# DRF1605_KIT.net
KiCad netlist of a schematic drawn in Altium Designer
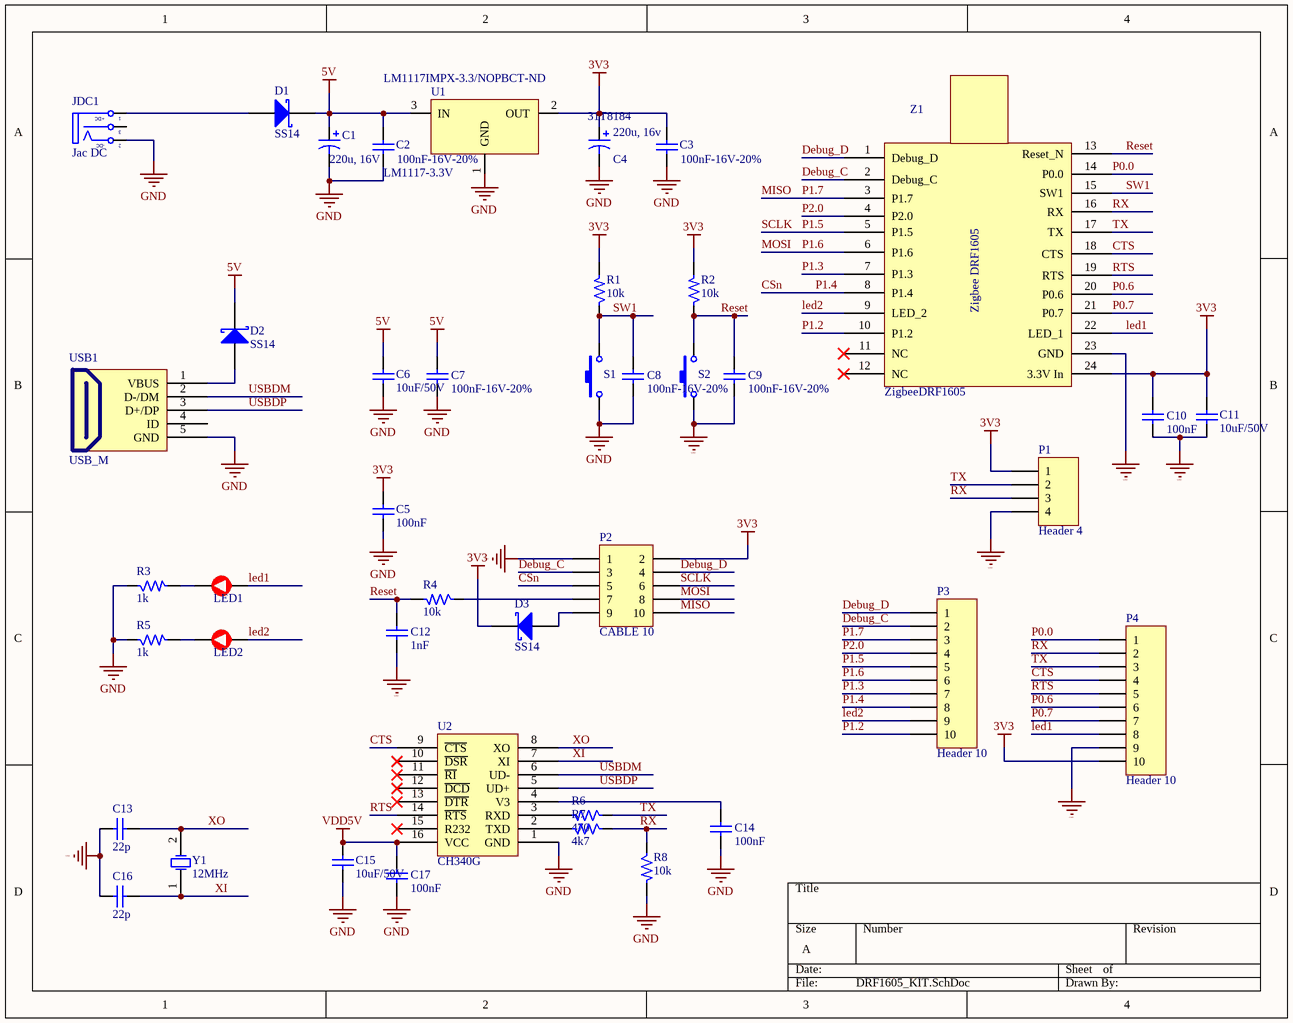
[diagram p0: DRF1605_KIT.SchDoc]

(export (version "E")
  (design (tool "Eeschema 10.0.6"))
  (components
    (comp (ref "C1")
      (value "220u, 16V")
      (footprint "ST:CAP TANTALUM 7343")
      (description "Polarized Capacitor (Surface Mount)")
      (fields
        (field (name "MANUFACTURER") "Kemet")
        (field (name "MANUFACTURER PART NUMBER") "C0603C103K5RACTU")
        (field (name "PUBLISHER") "Altium Limited")
      )
      (libsource (lib "Miscellaneous Devices") (part "Cap Pol3"))
    )
    (comp (ref "C2")
      (value "100nF-16V-20%")
      (footprint "C0805")
      (description "CAP CER 0.1UF 16V Y5V 0603")
      (fields
        (field (name "MANUFACTURER") "Yageo")
        (field (name "DIGI-KEY PART NUMBER") "311-1369-1-ND")
        (field (name "PUBLISHER") "Altium Limited")
      )
      (libsource (lib "Miscellaneous Devices") (part "Cap"))
    )
    (comp (ref "C3")
      (value "100nF-16V-20%")
      (footprint "C0805")
      (description "CAP CER 0.1UF 16V Y5V 0603")
      (fields
        (field (name "MANUFACTURER") "Yageo")
        (field (name "DIGI-KEY PART NUMBER") "311-1369-1-ND")
        (field (name "PUBLISHER") "Altium Limited")
      )
      (libsource (lib "Miscellaneous Devices") (part "Cap"))
    )
    (comp (ref "C4")
      (value "220u, 16v")
      (footprint "CAP TANTALUM 7343")
      (description "Polarized Capacitor (Surface Mount)")
      (fields (field (name "SUPPLIER PART NUMBER 1") "31T8184") (field (name "PUBLISHER") "Altium Limited"))
      (libsource (lib "Miscellaneous Devices") (part "Cap Pol3"))
    )
    (comp (ref "C5")
      (value "100nF")
      (footprint "C0805")
      (description "CAP CER 0.1UF 16V Y5V 0603")
      (fields
        (field (name "MANUFACTURER") "Yageo")
        (field (name "DIGI-KEY PART NUMBER") "311-1369-1-ND")
        (field (name "PUBLISHER") "Altium Limited")
      )
      (libsource (lib "Miscellaneous Devices") (part "Cap"))
    )
    (comp (ref "C6")
      (value "10uF/50V")
      (footprint "C1206")
      (description "Capacitor 100n 16V 0603")
      (fields (field (name "PUBLISHER") "Altium Limited"))
      (libsource (lib "Capacitor") (part "Cap Semi"))
    )
    (comp (ref "C7")
      (value "100nF-16V-20%")
      (footprint "C0805")
      (description "CAP CER 0.1UF 16V Y5V 0603")
      (fields
        (field (name "MANUFACTURER") "Yageo")
        (field (name "DIGI-KEY PART NUMBER") "311-1369-1-ND")
        (field (name "PUBLISHER") "Altium Limited")
      )
      (libsource (lib "Miscellaneous Devices") (part "Cap"))
    )
    (comp (ref "C8")
      (value "100nF-16V-20%")
      (footprint "C0805")
      (description "CAP CER 0.1UF 16V Y5V 0603")
      (fields
        (field (name "MANUFACTURER") "Yageo")
        (field (name "DIGI-KEY PART NUMBER") "311-1369-1-ND")
        (field (name "PUBLISHER") "Altium Limited")
      )
      (libsource (lib "Miscellaneous Devices") (part "Cap"))
    )
    (comp (ref "C9")
      (value "100nF-16V-20%")
      (footprint "C0805")
      (description "CAP CER 0.1UF 16V Y5V 0603")
      (fields
        (field (name "MANUFACTURER") "Yageo")
        (field (name "DIGI-KEY PART NUMBER") "311-1369-1-ND")
        (field (name "PUBLISHER") "Altium Limited")
      )
      (libsource (lib "Miscellaneous Devices") (part "Cap"))
    )
    (comp (ref "C10")
      (value "100nF")
      (footprint "C0805")
      (description "CAP CER 0.1UF 16V Y5V 0603")
      (fields
        (field (name "MANUFACTURER") "Yageo")
        (field (name "DIGI-KEY PART NUMBER") "311-1369-1-ND")
        (field (name "PUBLISHER") "Altium Limited")
      )
      (libsource (lib "Miscellaneous Devices") (part "Cap"))
    )
    (comp (ref "C11")
      (value "10uF/50V")
      (footprint "C1206")
      (description "Capacitor 100n 16V 0603")
      (fields (field (name "PUBLISHER") "Altium Limited"))
      (libsource (lib "Capacitor") (part "Cap Semi"))
    )
    (comp (ref "C12")
      (value "1nF")
      (footprint "C0805")
      (description "CAP CER 0.1UF 16V Y5V 0603")
      (fields
        (field (name "MANUFACTURER") "Yageo")
        (field (name "DIGI-KEY PART NUMBER") "311-1369-1-ND")
        (field (name "PUBLISHER") "Altium Limited")
      )
      (libsource (lib "Miscellaneous Devices") (part "Cap"))
    )
    (comp (ref "C13")
      (value "22p")
      (footprint "C0805")
      (description "Capacitor (Semiconductor SIM Model)")
      (fields (field (name "PUBLISHER") "Altium Limited"))
      (libsource (lib "Miscellaneous Devices") (part "Cap Semi"))
    )
    (comp (ref "C14")
      (value "100nF")
      (footprint "C0805")
      (description "CAP CER 0.1UF 16V Y5V 0603")
      (fields
        (field (name "MANUFACTURER") "Yageo")
        (field (name "DIGI-KEY PART NUMBER") "311-1369-1-ND")
        (field (name "PUBLISHER") "Altium Limited")
      )
      (libsource (lib "Miscellaneous Devices") (part "Cap"))
    )
    (comp (ref "C15")
      (value "10uF/50V")
      (footprint "C1206")
      (description "Capacitor 100n 16V 0603")
      (fields (field (name "PUBLISHER") "Altium Limited"))
      (libsource (lib "Capacitor") (part "Cap Semi"))
    )
    (comp (ref "C16")
      (value "22p")
      (footprint "C0805")
      (description "Capacitor (Semiconductor SIM Model)")
      (fields (field (name "PUBLISHER") "Altium Limited"))
      (libsource (lib "Miscellaneous Devices") (part "Cap Semi"))
    )
    (comp (ref "C17")
      (value "100nF")
      (footprint "C0805")
      (description "CAP CER 0.1UF 16V Y5V 0603")
      (fields
        (field (name "MANUFACTURER") "Yageo")
        (field (name "DIGI-KEY PART NUMBER") "311-1369-1-ND")
        (field (name "PUBLISHER") "Altium Limited")
      )
      (libsource (lib "Miscellaneous Devices") (part "Cap"))
    )
    (comp (ref "D1")
      (value "SS14")
      (footprint "DO-214AC (SMA)")
      (description "Schottky Diode")
      (fields (field (name "PUBLISHER") "Altium Limited"))
      (libsource (lib "Miscellaneous Devices") (part "D Schottky"))
    )
    (comp (ref "D2")
      (value "SS14")
      (footprint "DO-214AC (SMA)")
      (description "Schottky Diode")
      (fields (field (name "PUBLISHER") "Altium Limited"))
      (libsource (lib "Miscellaneous Devices") (part "D Schottky"))
    )
    (comp (ref "D3")
      (value "SS14")
      (footprint "DO-214AC (SMA)")
      (description "Schottky Diode")
      (fields (field (name "PUBLISHER") "Altium Limited"))
      (libsource (lib "Miscellaneous Devices") (part "D Schottky"))
    )
    (comp (ref "JDC1")
      (value "Jac DC")
      (footprint "DC-IN")
      (description "Jac DC input")
      (libsource (lib "syhaunguyen") (part "DCIN"))
    )
    (comp (ref "LED1")
      (value "LedBlue5")
      (footprint "LedBlue5")
      (description "LED")
      (fields (field (name "MANUFACTURER") "Harvatek"))
      (libsource (lib "SS_Basic") (part "Led"))
    )
    (comp (ref "LED2")
      (value "LedRed5")
      (footprint "LedRed5")
      (description "LED")
      (fields (field (name "MANUFACTURER") "Harvatek"))
      (libsource (lib "SS_Basic") (part "Led"))
    )
    (comp (ref "P1")
      (value "Header 4")
      (footprint "HDR1X4")
      (description "Header, 4-Pin")
      (fields (field (name "PUBLISHER") "Altium Limited"))
      (libsource (lib "SS_Con") (part "Header 4"))
    )
    (comp (ref "P2")
      (value "CABLE 10")
      (footprint "PcbLib2:CABLE 10")
      (description "Header, 5-Pin, Dual row")
      (fields (field (name "PUBLISHER") "Altium Limited"))
      (libsource (lib "mLibrary") (part "CABLE 10"))
    )
    (comp (ref "P3")
      (value "Header 10")
      (footprint "HDR1X10")
      (description "Header, 10-Pin")
      (fields (field (name "PUBLISHER") "Altium Limited"))
      (libsource (lib "SS_Con") (part "Header 10"))
    )
    (comp (ref "P4")
      (value "Header 10")
      (footprint "HDR1X10")
      (description "Header, 10-Pin")
      (fields (field (name "PUBLISHER") "Altium Limited"))
      (libsource (lib "SS_Con") (part "Header 10"))
    )
    (comp (ref "R1")
      (value "10k")
      (footprint "R0805")
      (description "Resistor SMD")
      (fields (field (name "MANUFACTURER") "UniOhm"))
      (libsource (lib "Schlib1") (part "RM"))
    )
    (comp (ref "R2")
      (value "10k")
      (footprint "R0805")
      (description "Resistor SMD")
      (fields (field (name "MANUFACTURER") "UniOhm"))
      (libsource (lib "Schlib1") (part "RM"))
    )
    (comp (ref "R3")
      (value "1k")
      (footprint "R0805")
      (description "Resistor SMD")
      (fields (field (name "MANUFACTURER") "UniOhm"))
      (libsource (lib "Schlib1") (part "RM"))
    )
    (comp (ref "R4")
      (value "10k")
      (footprint "R0805")
      (description "Resistor SMD")
      (fields (field (name "MANUFACTURER") "UniOhm"))
      (libsource (lib "Schlib1") (part "RM"))
    )
    (comp (ref "R5")
      (value "1k")
      (footprint "R0805")
      (description "Resistor SMD")
      (fields (field (name "MANUFACTURER") "UniOhm"))
      (libsource (lib "Schlib1") (part "RM"))
    )
    (comp (ref "R6")
      (value "470")
      (footprint "R0805")
      (description "Resistor SMD")
      (fields (field (name "MANUFACTURER") "UniOhm"))
      (libsource (lib "Schlib1") (part "RM"))
    )
    (comp (ref "R7")
      (value "4k7")
      (footprint "R0805")
      (description "Resistor SMD")
      (fields (field (name "MANUFACTURER") "UniOhm"))
      (libsource (lib "Schlib1") (part "RM"))
    )
    (comp (ref "R8")
      (value "10k")
      (footprint "R0805")
      (description "Resistor SMD")
      (fields (field (name "MANUFACTURER") "UniOhm"))
      (libsource (lib "Schlib1") (part "RM"))
    )
    (comp (ref "S1")
      (value "SW-SMD")
      (footprint "Button Tactile Switch")
      (description "Switch")
      (fields (field (name "PUBLISHER") "Altium Limited"))
      (libsource (lib "Schematic") (part "SW-SMD"))
    )
    (comp (ref "S2")
      (value "SW-SMD")
      (footprint "Button Tactile Switch")
      (description "Switch")
      (fields (field (name "PUBLISHER") "Altium Limited"))
      (libsource (lib "Schematic") (part "SW-SMD"))
    )
    (comp (ref "U1")
      (value "LM1117-3.3V")
      (footprint "LM1117-SOP")
      (description "800mA Low-Dropout Linear Regulator")
      (fields
        (field (name "SUPPLIER PART NUMBER 1") "LM1117IMPX-3.3/NOPBCT-ND")
        (field (name "CREATOR") "Nguyen Ba Bien")
      )
      (libsource (lib "General IC") (part "LM1117"))
    )
    (comp (ref "U2")
      (value "CH340G")
      (footprint "SOP-16")
      (description "CH340G USB to serial (UART) bridge")
      (libsource (lib "Vowstar_IC_General") (part "CH340G"))
    )
    (comp (ref "USB1") (value "USB_M") (footprint "USB_B_MINI_SMD") (libsource (lib "SS_Con") (part "USB_M")))
    (comp (ref "Y1")
      (value "12MHz")
      (footprint "ST:XT2 SMD")
      (description "Crystal Oscillator")
      (fields (field (name "PUBLISHER") "Altium Limited"))
      (libsource (lib "Miscellaneous Devices") (part "XTAL"))
    )
    (comp (ref "Z1")
      (value "ZigbeeDRF1605")
      (footprint "PcbLib2:DRF1605")
      (libsource (lib "module-lib") (part "DRF1605"))
    )
  )
  (nets
    (net (code "1") (name "/CSn") (class "Default")
      (node (ref "P2") (pin "5") (pinfunction "5_5") (pintype "passive"))
      (node (ref "P3") (pin "8") (pinfunction "8_8") (pintype "passive"))
      (node (ref "Z1") (pin "8") (pinfunction "P1.4_8") (pintype "passive"))
    )
    (net (code "2") (name "/CTS") (class "Default")
      (node (ref "P4") (pin "4") (pinfunction "4_4") (pintype "passive"))
      (node (ref "U2") (pin "9") (pinfunction "~{CTS}_9") (pintype "passive"))
      (node (ref "Z1") (pin "18") (pinfunction "CTS_18") (pintype "passive"))
    )
    (net (code "3") (name "/Debug_C") (class "Default")
      (node (ref "P2") (pin "3") (pinfunction "3_3") (pintype "passive"))
      (node (ref "P3") (pin "2") (pinfunction "2_2") (pintype "passive"))
      (node (ref "Z1") (pin "2") (pinfunction "Debug_C_2") (pintype "passive"))
    )
    (net (code "4") (name "/Debug_D") (class "Default")
      (node (ref "P2") (pin "4") (pinfunction "4_4") (pintype "passive"))
      (node (ref "P3") (pin "1") (pinfunction "1_1") (pintype "passive"))
      (node (ref "Z1") (pin "1") (pinfunction "Debug_D_1") (pintype "passive"))
    )
    (net (code "5") (name "/MISO") (class "Default")
      (node (ref "P2") (pin "10") (pinfunction "10_10") (pintype "passive"))
      (node (ref "P3") (pin "3") (pinfunction "3_3") (pintype "passive"))
      (node (ref "Z1") (pin "3") (pinfunction "P1.7_3") (pintype "passive"))
    )
    (net (code "6") (name "/MOSI") (class "Default")
      (node (ref "P2") (pin "8") (pinfunction "8_8") (pintype "passive"))
      (node (ref "P3") (pin "6") (pinfunction "6_6") (pintype "passive"))
      (node (ref "Z1") (pin "6") (pinfunction "P1.6_6") (pintype "passive"))
    )
    (net (code "7") (name "/P0.0") (class "Default")
      (node (ref "P4") (pin "1") (pinfunction "1_1") (pintype "passive"))
      (node (ref "Z1") (pin "14") (pinfunction "P0.0_14") (pintype "passive"))
    )
    (net (code "8") (name "/P0.6") (class "Default")
      (node (ref "P4") (pin "6") (pinfunction "6_6") (pintype "passive"))
      (node (ref "Z1") (pin "20") (pinfunction "P0.6_20") (pintype "passive"))
    )
    (net (code "9") (name "/P0.7") (class "Default")
      (node (ref "P4") (pin "7") (pinfunction "7_7") (pintype "passive"))
      (node (ref "Z1") (pin "21") (pinfunction "P0.7_21") (pintype "passive"))
    )
    (net (code "10") (name "/P1.2") (class "Default")
      (node (ref "P3") (pin "10") (pinfunction "10_10") (pintype "passive"))
      (node (ref "Z1") (pin "10") (pinfunction "P1.2_10") (pintype "passive"))
    )
    (net (code "11") (name "/P1.3") (class "Default")
      (node (ref "P3") (pin "7") (pinfunction "7_7") (pintype "passive"))
      (node (ref "Z1") (pin "7") (pinfunction "P1.3_7") (pintype "passive"))
    )
    (net (code "12") (name "/P1.5") (class "Default")
      (node (ref "P2") (pin "6") (pinfunction "6_6") (pintype "passive"))
      (node (ref "P3") (pin "5") (pinfunction "5_5") (pintype "passive"))
      (node (ref "Z1") (pin "5") (pinfunction "P1.5_5") (pintype "passive"))
    )
    (net (code "13") (name "/P2.0") (class "Default")
      (node (ref "P3") (pin "4") (pinfunction "4_4") (pintype "passive"))
      (node (ref "Z1") (pin "4") (pinfunction "P2.0_4") (pintype "passive"))
    )
    (net (code "14") (name "/RTS") (class "Default")
      (node (ref "P4") (pin "5") (pinfunction "5_5") (pintype "passive"))
      (node (ref "U2") (pin "14") (pinfunction "~{RTS}_14") (pintype "passive"))
      (node (ref "Z1") (pin "19") (pinfunction "RTS_19") (pintype "passive"))
    )
    (net (code "15") (name "/RX") (class "Default")
      (node (ref "P1") (pin "3") (pinfunction "3_3") (pintype "passive"))
      (node (ref "P4") (pin "2") (pinfunction "2_2") (pintype "passive"))
      (node (ref "R7") (pin "1") (pinfunction "1_1") (pintype "passive"))
      (node (ref "R8") (pin "1") (pinfunction "1_1") (pintype "passive"))
      (node (ref "Z1") (pin "16") (pinfunction "RX_16") (pintype "passive"))
    )
    (net (code "16") (name "/Reset") (class "Default")
      (node (ref "C12") (pin "1") (pinfunction "1_1") (pintype "passive"))
      (node (ref "C9") (pin "1") (pinfunction "1_1") (pintype "passive"))
      (node (ref "R2") (pin "1") (pinfunction "1_1") (pintype "passive"))
      (node (ref "R4") (pin "2") (pinfunction "2_2") (pintype "passive"))
      (node (ref "S2") (pin "2") (pinfunction "2_2") (pintype "passive"))
      (node (ref "Z1") (pin "13") (pinfunction "Reset_N_13") (pintype "passive"))
    )
    (net (code "17") (name "/SW1") (class "Default")
      (node (ref "C8") (pin "1") (pinfunction "1_1") (pintype "passive"))
      (node (ref "R1") (pin "1") (pinfunction "1_1") (pintype "passive"))
      (node (ref "S1") (pin "2") (pinfunction "2_2") (pintype "passive"))
      (node (ref "Z1") (pin "15") (pinfunction "SW1_15") (pintype "passive"))
    )
    (net (code "18") (name "/TX") (class "Default")
      (node (ref "P1") (pin "2") (pinfunction "2_2") (pintype "passive"))
      (node (ref "P4") (pin "3") (pinfunction "3_3") (pintype "passive"))
      (node (ref "R6") (pin "1") (pinfunction "1_1") (pintype "passive"))
      (node (ref "Z1") (pin "17") (pinfunction "TX_17") (pintype "passive"))
    )
    (net (code "19") (name "/USBDM") (class "Default")
      (node (ref "U2") (pin "6") (pinfunction "UD-_6") (pintype "passive"))
      (node (ref "USB1") (pin "2") (pinfunction "D-/DM_2") (pintype "passive"))
    )
    (net (code "20") (name "/USBDP") (class "Default")
      (node (ref "U2") (pin "5") (pinfunction "UD+_5") (pintype "passive"))
      (node (ref "USB1") (pin "3") (pinfunction "D+/DP_3") (pintype "passive"))
    )
    (net (code "21") (name "/XI") (class "Default")
      (node (ref "C16") (pin "2") (pinfunction "2_2") (pintype "passive"))
      (node (ref "U2") (pin "7") (pinfunction "XI_7") (pintype "passive"))
      (node (ref "Y1") (pin "1") (pinfunction "OSC1_1") (pintype "passive"))
    )
    (net (code "22") (name "/XO") (class "Default")
      (node (ref "C13") (pin "2") (pinfunction "2_2") (pintype "passive"))
      (node (ref "U2") (pin "8") (pinfunction "XO_8") (pintype "passive"))
      (node (ref "Y1") (pin "2") (pinfunction "OSC2_2") (pintype "passive"))
    )
    (net (code "23") (name "/led1") (class "Default")
      (node (ref "LED1") (pin "2") (pinfunction "2_2") (pintype "passive"))
      (node (ref "P4") (pin "8") (pinfunction "8_8") (pintype "passive"))
      (node (ref "Z1") (pin "22") (pinfunction "LED_1_22") (pintype "passive"))
    )
    (net (code "24") (name "/led2") (class "Default")
      (node (ref "LED2") (pin "2") (pinfunction "2_2") (pintype "passive"))
      (node (ref "P3") (pin "9") (pinfunction "9_9") (pintype "passive"))
      (node (ref "Z1") (pin "9") (pinfunction "LED_2_9") (pintype "passive"))
    )
    (net (code "25") (name "3V3") (class "Default")
      (node (ref "C10") (pin "1") (pinfunction "1_1") (pintype "passive"))
      (node (ref "C11") (pin "1") (pinfunction "1_1") (pintype "passive"))
      (node (ref "C3") (pin "1") (pinfunction "1_1") (pintype "passive"))
      (node (ref "C4") (pin "1") (pinfunction "1_1") (pintype "passive"))
      (node (ref "C5") (pin "1") (pinfunction "1_1") (pintype "passive"))
      (node (ref "D3") (pin "2") (pinfunction "K_2") (pintype "passive"))
      (node (ref "P1") (pin "1") (pinfunction "1_1") (pintype "passive"))
      (node (ref "P2") (pin "2") (pinfunction "2_2") (pintype "passive"))
      (node (ref "P4") (pin "10") (pinfunction "10_10") (pintype "passive"))
      (node (ref "R1") (pin "2") (pinfunction "2_2") (pintype "passive"))
      (node (ref "R2") (pin "2") (pinfunction "2_2") (pintype "passive"))
      (node (ref "U1") (pin "2") (pinfunction "OUT_2") (pintype "passive"))
      (node (ref "Z1") (pin "24") (pinfunction "3.3V_In_24") (pintype "passive"))
    )
    (net (code "26") (name "5V") (class "Default")
      (node (ref "C1") (pin "1") (pinfunction "1_1") (pintype "passive"))
      (node (ref "C2") (pin "1") (pinfunction "1_1") (pintype "passive"))
      (node (ref "C6") (pin "1") (pinfunction "1_1") (pintype "passive"))
      (node (ref "C7") (pin "1") (pinfunction "1_1") (pintype "passive"))
      (node (ref "D1") (pin "2") (pinfunction "K_2") (pintype "passive"))
      (node (ref "D2") (pin "2") (pinfunction "K_2") (pintype "passive"))
      (node (ref "U1") (pin "3") (pinfunction "IN_3") (pintype "passive"))
    )
    (net (code "27") (name "GND") (class "Default")
      (node (ref "C1") (pin "2") (pinfunction "2_2") (pintype "passive"))
      (node (ref "C10") (pin "2") (pinfunction "2_2") (pintype "passive"))
      (node (ref "C11") (pin "2") (pinfunction "2_2") (pintype "passive"))
      (node (ref "C12") (pin "2") (pinfunction "2_2") (pintype "passive"))
      (node (ref "C13") (pin "1") (pinfunction "1_1") (pintype "passive"))
      (node (ref "C14") (pin "2") (pinfunction "2_2") (pintype "passive"))
      (node (ref "C15") (pin "2") (pinfunction "2_2") (pintype "passive"))
      (node (ref "C16") (pin "1") (pinfunction "1_1") (pintype "passive"))
      (node (ref "C17") (pin "2") (pinfunction "2_2") (pintype "passive"))
      (node (ref "C2") (pin "2") (pinfunction "2_2") (pintype "passive"))
      (node (ref "C3") (pin "2") (pinfunction "2_2") (pintype "passive"))
      (node (ref "C4") (pin "2") (pinfunction "2_2") (pintype "passive"))
      (node (ref "C5") (pin "2") (pinfunction "2_2") (pintype "passive"))
      (node (ref "C6") (pin "2") (pinfunction "2_2") (pintype "passive"))
      (node (ref "C7") (pin "2") (pinfunction "2_2") (pintype "passive"))
      (node (ref "C8") (pin "2") (pinfunction "2_2") (pintype "passive"))
      (node (ref "C9") (pin "2") (pinfunction "2_2") (pintype "passive"))
      (node (ref "JDC1") (pin "2") (pinfunction "TN_2") (pintype "passive"))
      (node (ref "P1") (pin "4") (pinfunction "4_4") (pintype "passive"))
      (node (ref "P2") (pin "1") (pinfunction "1_1") (pintype "passive"))
      (node (ref "P4") (pin "9") (pinfunction "9_9") (pintype "passive"))
      (node (ref "R3") (pin "1") (pinfunction "1_1") (pintype "passive"))
      (node (ref "R5") (pin "1") (pinfunction "1_1") (pintype "passive"))
      (node (ref "R8") (pin "2") (pinfunction "2_2") (pintype "passive"))
      (node (ref "S1") (pin "1") (pinfunction "1_1") (pintype "passive"))
      (node (ref "S2") (pin "1") (pinfunction "1_1") (pintype "passive"))
      (node (ref "U1") (pin "1") (pinfunction "GND_1") (pintype "passive"))
      (node (ref "U2") (pin "1") (pinfunction "GND_1") (pintype "passive"))
      (node (ref "USB1") (pin "5") (pinfunction "GND_5") (pintype "passive"))
      (node (ref "Z1") (pin "23") (pinfunction "GND_23") (pintype "passive"))
    )
    (net (code "28") (name "Net-(D1-A)") (class "Default")
      (node (ref "D1") (pin "1") (pinfunction "A_1") (pintype "passive"))
      (node (ref "JDC1") (pin "1") (pinfunction "T_1") (pintype "passive"))
    )
    (net (code "29") (name "Net-(D2-A)") (class "Default")
      (node (ref "D2") (pin "1") (pinfunction "A_1") (pintype "passive"))
      (node (ref "USB1") (pin "1") (pinfunction "VBUS_1") (pintype "passive"))
    )
    (net (code "30") (name "Net-(D3-A)") (class "Default")
      (node (ref "D3") (pin "1") (pinfunction "A_1") (pintype "passive"))
      (node (ref "P2") (pin "9") (pinfunction "9_9") (pintype "passive"))
    )
    (net (code "31") (name "Net-(LED1-Pad1)") (class "Default")
      (node (ref "LED1") (pin "1") (pinfunction "1_1") (pintype "passive"))
      (node (ref "R3") (pin "2") (pinfunction "2_2") (pintype "passive"))
    )
    (net (code "32") (name "Net-(LED2-Pad1)") (class "Default")
      (node (ref "LED2") (pin "1") (pinfunction "1_1") (pintype "passive"))
      (node (ref "R5") (pin "2") (pinfunction "2_2") (pintype "passive"))
    )
    (net (code "33") (name "Net-(P2-Pad7)") (class "Default")
      (node (ref "P2") (pin "7") (pinfunction "7_7") (pintype "passive"))
      (node (ref "R4") (pin "1") (pinfunction "1_1") (pintype "passive"))
    )
    (net (code "34") (name "Net-(U2-RXD)") (class "Default")
      (node (ref "R6") (pin "2") (pinfunction "2_2") (pintype "passive"))
      (node (ref "U2") (pin "3") (pinfunction "RXD_3") (pintype "passive"))
    )
    (net (code "35") (name "Net-(U2-TXD)") (class "Default")
      (node (ref "R7") (pin "2") (pinfunction "2_2") (pintype "passive"))
      (node (ref "U2") (pin "2") (pinfunction "TXD_2") (pintype "passive"))
    )
    (net (code "36") (name "Net-(U2-V3)") (class "Default")
      (node (ref "C14") (pin "1") (pinfunction "1_1") (pintype "passive"))
      (node (ref "U2") (pin "4") (pinfunction "V3_4") (pintype "passive"))
    )
    (net (code "37") (name "VDD5V") (class "Default")
      (node (ref "C15") (pin "1") (pinfunction "1_1") (pintype "passive"))
      (node (ref "C17") (pin "1") (pinfunction "1_1") (pintype "passive"))
      (node (ref "U2") (pin "16") (pinfunction "VCC_16") (pintype "passive"))
    )
    (net (code "38") (name "unconnected-(JDC1-S-Pad3)") (class "Default")
      (node (ref "JDC1") (pin "3") (pinfunction "S_3") (pintype "power_in"))
    )
    (net (code "39") (name "unconnected-(U2-R232-Pad15)") (class "Default")
      (node (ref "U2") (pin "15") (pinfunction "R232_15") (pintype "passive+no_connect"))
    )
    (net (code "40") (name "unconnected-(U2-~{DCD}-Pad12)") (class "Default")
      (node (ref "U2") (pin "12") (pinfunction "~{DCD}_12") (pintype "passive+no_connect"))
    )
    (net (code "41") (name "unconnected-(U2-~{DSR}-Pad10)") (class "Default")
      (node (ref "U2") (pin "10") (pinfunction "~{DSR}_10") (pintype "passive+no_connect"))
    )
    (net (code "42") (name "unconnected-(U2-~{DTR}-Pad13)") (class "Default")
      (node (ref "U2") (pin "13") (pinfunction "~{DTR}_13") (pintype "passive+no_connect"))
    )
    (net (code "43") (name "unconnected-(U2-~{RI}-Pad11)") (class "Default")
      (node (ref "U2") (pin "11") (pinfunction "~{RI}_11") (pintype "passive+no_connect"))
    )
    (net (code "44") (name "unconnected-(USB1-ID-Pad4)") (class "Default")
      (node (ref "USB1") (pin "4") (pinfunction "ID_4") (pintype "passive"))
    )
    (net (code "45") (name "unconnected-(Z1-NC-Pad11)") (class "Default")
      (node (ref "Z1") (pin "11") (pinfunction "NC_11") (pintype "passive+no_connect"))
    )
    (net (code "46") (name "unconnected-(Z1-NC-Pad12)") (class "Default")
      (node (ref "Z1") (pin "12") (pinfunction "NC_12") (pintype "passive+no_connect"))
    )
  )
)
